# DigitalV0_1.net
KiCad netlist of a schematic drawn in Altium Designer
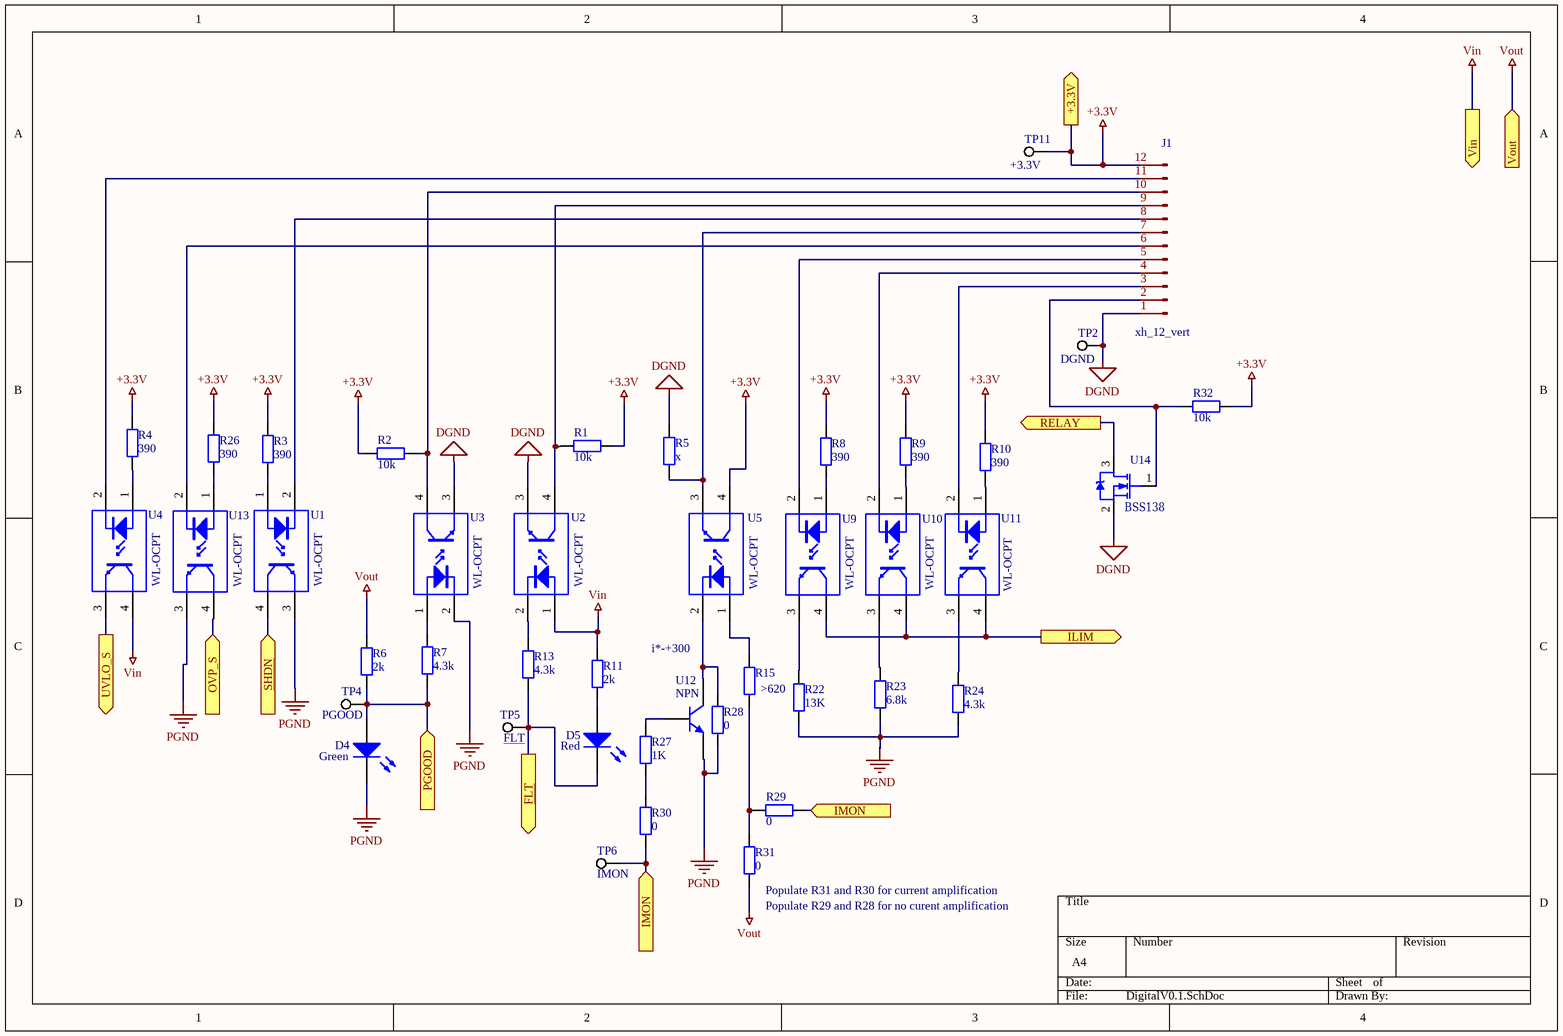
[diagram p0: DigitalV0.1.SchDoc]

(export (version "E")
  (design (tool "Eeschema 10.0.6"))
  (components
    (comp (ref "D4")
      (value "Green")
      (footprint "0805 LED")
      (libsource (lib "generic_components") (part "LED"))
    )
    (comp (ref "D5") (value "Red") (footprint "0805 LED") (libsource (lib "generic_components") (part "LED")))
    (comp (ref "J1")
      (value "xh_12_vert")
      (footprint "JST_XH_B12B-XH-A_1x12_P2.50mm_Vertical")
      (libsource (lib "JST") (part "xh_12_vert"))
    )
    (comp (ref "R1") (value "10k") (footprint "0805") (libsource (lib "") (part "res0805_2")))
    (comp (ref "R2") (value "10k") (footprint "0805") (libsource (lib "") (part "res0805_3")))
    (comp (ref "R3") (value "390") (footprint "0805") (libsource (lib "") (part "res0805_1")))
    (comp (ref "R4") (value "390") (footprint "0805") (libsource (lib "") (part "res0805_1")))
    (comp (ref "R5") (value "x") (footprint "0805") (libsource (lib "") (part "res0805_1")))
    (comp (ref "R6") (value "2k") (footprint "0805") (libsource (lib "") (part "res0805_1")))
    (comp (ref "R7") (value "4.3k") (footprint "0805") (libsource (lib "") (part "res0805_1")))
    (comp (ref "R8") (value "390") (footprint "0805") (libsource (lib "") (part "res0805_1")))
    (comp (ref "R9") (value "390") (footprint "0805") (libsource (lib "") (part "res0805_1")))
    (comp (ref "R10") (value "390") (footprint "0805") (libsource (lib "") (part "res0805_1")))
    (comp (ref "R11") (value "2k") (footprint "0805") (libsource (lib "") (part "res0805_1")))
    (comp (ref "R13") (value "4.3k") (footprint "0805") (libsource (lib "") (part "res0805_1")))
    (comp (ref "R15") (value ">620") (footprint "0805") (libsource (lib "") (part "res0805_1")))
    (comp (ref "R22") (value "13K") (footprint "0805") (libsource (lib "") (part "res0805_1")))
    (comp (ref "R23") (value "6.8k") (footprint "0805") (libsource (lib "") (part "res0805_1")))
    (comp (ref "R24") (value "4.3k") (footprint "0805") (libsource (lib "") (part "res0805_1")))
    (comp (ref "R26") (value "390") (footprint "0805") (libsource (lib "") (part "res0805_1")))
    (comp (ref "R27") (value "1K") (footprint "0805") (libsource (lib "generic_components") (part "res0805")))
    (comp (ref "R28") (value "0") (footprint "0805") (libsource (lib "generic_components") (part "res0805")))
    (comp (ref "R29") (value "0") (footprint "0805") (libsource (lib "") (part "res0805_2")))
    (comp (ref "R30") (value "0") (footprint "0805") (libsource (lib "generic_components") (part "res0805")))
    (comp (ref "R31") (value "0") (footprint "0805") (libsource (lib "generic_components") (part "res0805")))
    (comp (ref "R32") (value "10k") (footprint "0805") (libsource (lib "") (part "res0805_3")))
    (comp (ref "TP2")
      (value "DGND")
      (footprint "Test Loop 1.6mm")
      (libsource (lib "generic_components") (part "Test point"))
    )
    (comp (ref "TP4")
      (value "PGOOD")
      (footprint "Test Loop 1.6mm")
      (libsource (lib "generic_components") (part "Test point"))
    )
    (comp (ref "TP5")
      (value "FLT")
      (footprint "Test Loop 1.6mm")
      (libsource (lib "generic_components") (part "Test point"))
    )
    (comp (ref "TP6")
      (value "IMON")
      (footprint "Test Loop 1.6mm")
      (libsource (lib "generic_components") (part "Test point"))
    )
    (comp (ref "TP11")
      (value "+3.3V")
      (footprint "Test Loop 1.6mm")
      (libsource (lib "generic_components") (part "Test point"))
    )
    (comp (ref "U1")
      (value "WL-OCPT")
      (footprint "4-SOP_WE_opto-isolator")
      (libsource (lib "generic_components") (part "optoc WE"))
    )
    (comp (ref "U2")
      (value "WL-OCPT")
      (footprint "4-SOP_WE_opto-isolator")
      (libsource (lib "generic_components") (part "optoc WE"))
    )
    (comp (ref "U3")
      (value "WL-OCPT")
      (footprint "4-SOP_WE_opto-isolator")
      (libsource (lib "generic_components") (part "optoc WE"))
    )
    (comp (ref "U4")
      (value "WL-OCPT")
      (footprint "4-SOP_WE_opto-isolator")
      (libsource (lib "generic_components") (part "optoc WE"))
    )
    (comp (ref "U5")
      (value "WL-OCPT")
      (footprint "4-SOP_WE_opto-isolator")
      (libsource (lib "generic_components") (part "optoc WE"))
    )
    (comp (ref "U9")
      (value "WL-OCPT")
      (footprint "4-SOP_WE_opto-isolator")
      (libsource (lib "generic_components") (part "optoc WE"))
    )
    (comp (ref "U10")
      (value "WL-OCPT")
      (footprint "4-SOP_WE_opto-isolator")
      (libsource (lib "generic_components") (part "optoc WE"))
    )
    (comp (ref "U11")
      (value "WL-OCPT")
      (footprint "4-SOP_WE_opto-isolator")
      (libsource (lib "generic_components") (part "optoc WE"))
    )
    (comp (ref "U12")
      (value "NPN")
      (footprint "SOT23(TO-236AB)P095S230x290")
      (libsource (lib "generic_components") (part "NPN"))
    )
    (comp (ref "U13")
      (value "WL-OCPT")
      (footprint "4-SOP_WE_opto-isolator")
      (libsource (lib "generic_components") (part "optoc WE"))
    )
    (comp (ref "U14")
      (value "BSS138‎")
      (footprint "SOT-23-3")
      (libsource (lib "generic_components") (part "N-mosfet en"))
    )
  )
  (nets
    (net (code "1") (name "+3.3V") (class "Default")
      (node (ref "J1") (pin "12") (pinfunction "Pin_11_12") (pintype "passive"))
      (node (ref "R1") (pin "1") (pintype "passive"))
      (node (ref "R10") (pin "2") (pinfunction "2_2") (pintype "passive"))
      (node (ref "R2") (pin "1") (pintype "passive"))
      (node (ref "R26") (pin "2") (pinfunction "2_2") (pintype "passive"))
      (node (ref "R3") (pin "2") (pinfunction "2_2") (pintype "passive"))
      (node (ref "R32") (pin "2") (pinfunction "2_2") (pintype "passive"))
      (node (ref "R4") (pin "2") (pinfunction "2_2") (pintype "passive"))
      (node (ref "R8") (pin "2") (pinfunction "2_2") (pintype "passive"))
      (node (ref "R9") (pin "2") (pinfunction "2_2") (pintype "passive"))
      (node (ref "TP11") (pin "1") (pintype "passive"))
      (node (ref "U5") (pin "4") (pinfunction "C_4") (pintype "passive"))
    )
    (net (code "2") (name "/FLT") (class "Default")
      (node (ref "D5") (pin "2") (pinfunction "K_2") (pintype "passive"))
      (node (ref "R13") (pin "1") (pintype "passive"))
      (node (ref "TP5") (pin "1") (pintype "passive"))
    )
    (net (code "3") (name "/ILIM") (class "Default")
      (node (ref "U10") (pin "4") (pinfunction "C_4") (pintype "passive"))
      (node (ref "U11") (pin "4") (pinfunction "C_4") (pintype "passive"))
      (node (ref "U9") (pin "4") (pinfunction "C_4") (pintype "passive"))
    )
    (net (code "4") (name "/IMON") (class "Default")
      (node (ref "R29") (pin "1") (pintype "passive"))
      (node (ref "R30") (pin "2") (pinfunction "2_2") (pintype "passive"))
      (node (ref "TP6") (pin "1") (pintype "passive"))
    )
    (net (code "5") (name "/OVP_S") (class "Default")
      (node (ref "U13") (pin "4") (pinfunction "C_4") (pintype "passive"))
    )
    (net (code "6") (name "/PGOOD") (class "Default")
      (node (ref "D4") (pin "1") (pinfunction "A_1") (pintype "passive"))
      (node (ref "R6") (pin "1") (pintype "passive"))
      (node (ref "R7") (pin "1") (pintype "passive"))
      (node (ref "TP4") (pin "1") (pintype "passive"))
    )
    (net (code "7") (name "/RELAY") (class "Default")
      (node (ref "U14") (pin "3") (pinfunction "S_3") (pintype "passive"))
    )
    (net (code "8") (name "/SHDN") (class "Default")
      (node (ref "U1") (pin "4") (pinfunction "C_4") (pintype "passive"))
    )
    (net (code "9") (name "/UVLO_S") (class "Default")
      (node (ref "U4") (pin "3") (pinfunction "E_3") (pintype "passive"))
    )
    (net (code "10") (name "DGND") (class "Default")
      (node (ref "J1") (pin "1") (pinfunction "Pin_1_1") (pintype "passive"))
      (node (ref "R5") (pin "2") (pinfunction "2_2") (pintype "passive"))
      (node (ref "TP2") (pin "1") (pintype "passive"))
      (node (ref "U14") (pin "2") (pinfunction "D_2") (pintype "passive"))
      (node (ref "U2") (pin "3") (pinfunction "E_3") (pintype "passive"))
      (node (ref "U3") (pin "3") (pinfunction "E_3") (pintype "passive"))
    )
    (net (code "11") (name "Net-(D5-A)") (class "Default")
      (node (ref "D5") (pin "1") (pinfunction "A_1") (pintype "passive"))
      (node (ref "R11") (pin "1") (pintype "passive"))
    )
    (net (code "12") (name "Net-(J1-Pin_2)") (class "Default")
      (node (ref "J1") (pin "2") (pinfunction "Pin_2_2") (pintype "passive"))
      (node (ref "R32") (pin "1") (pintype "passive"))
      (node (ref "U14") (pin "1") (pinfunction "G_1") (pintype "passive"))
    )
    (net (code "13") (name "Net-(J1-Pin_3)") (class "Default")
      (node (ref "J1") (pin "3") (pinfunction "Pin_3_3") (pintype "passive"))
      (node (ref "U11") (pin "2") (pinfunction "C_2") (pintype "passive"))
    )
    (net (code "14") (name "Net-(J1-Pin_4)") (class "Default")
      (node (ref "J1") (pin "4") (pinfunction "Pin_4_4") (pintype "passive"))
      (node (ref "U10") (pin "2") (pinfunction "C_2") (pintype "passive"))
    )
    (net (code "15") (name "Net-(J1-Pin_5)") (class "Default")
      (node (ref "J1") (pin "5") (pinfunction "Pin_5_5") (pintype "passive"))
      (node (ref "U9") (pin "2") (pinfunction "C_2") (pintype "passive"))
    )
    (net (code "16") (name "Net-(J1-Pin_6)") (class "Default")
      (node (ref "J1") (pin "6") (pinfunction "Pin_6_6") (pintype "passive"))
      (node (ref "U13") (pin "2") (pinfunction "C_2") (pintype "passive"))
    )
    (net (code "17") (name "Net-(J1-Pin_7)") (class "Default")
      (node (ref "J1") (pin "7") (pinfunction "Pin_7_7") (pintype "passive"))
      (node (ref "R5") (pin "1") (pintype "passive"))
      (node (ref "U5") (pin "3") (pinfunction "E_3") (pintype "passive"))
    )
    (net (code "18") (name "Net-(J1-Pin_8)") (class "Default")
      (node (ref "J1") (pin "8") (pinfunction "Pin_8_8") (pintype "passive"))
      (node (ref "U1") (pin "2") (pinfunction "C_2") (pintype "passive"))
    )
    (net (code "19") (name "Net-(J1-Pin_9)") (class "Default")
      (node (ref "J1") (pin "9") (pinfunction "Pin_9_9") (pintype "passive"))
      (node (ref "R1") (pin "2") (pinfunction "2_2") (pintype "passive"))
      (node (ref "U2") (pin "4") (pinfunction "C_4") (pintype "passive"))
    )
    (net (code "20") (name "Net-(J1-Pin_10)") (class "Default")
      (node (ref "J1") (pin "10") (pinfunction "Pin_10_10") (pintype "passive"))
      (node (ref "R2") (pin "2") (pinfunction "2_2") (pintype "passive"))
      (node (ref "U3") (pin "4") (pinfunction "C_4") (pintype "passive"))
    )
    (net (code "21") (name "Net-(J1-Pin_11-Pad11)") (class "Default")
      (node (ref "J1") (pin "11") (pinfunction "Pin_11_11") (pintype "passive"))
      (node (ref "U4") (pin "2") (pinfunction "C_2") (pintype "passive"))
    )
    (net (code "22") (name "Net-(R13-Pad2)") (class "Default")
      (node (ref "R13") (pin "2") (pinfunction "2_2") (pintype "passive"))
      (node (ref "U2") (pin "2") (pinfunction "C_2") (pintype "passive"))
    )
    (net (code "23") (name "Net-(R15-Pad1)") (class "Default")
      (node (ref "R15") (pin "1") (pintype "passive"))
      (node (ref "R29") (pin "2") (pinfunction "2_2") (pintype "passive"))
      (node (ref "R31") (pin "1") (pintype "passive"))
    )
    (net (code "24") (name "Net-(R27-Pad2)") (class "Default")
      (node (ref "R27") (pin "2") (pinfunction "2_2") (pintype "passive"))
      (node (ref "R30") (pin "1") (pintype "passive"))
    )
    (net (code "25") (name "Net-(U1-A)") (class "Default")
      (node (ref "R3") (pin "1") (pintype "passive"))
      (node (ref "U1") (pin "1") (pinfunction "A_1") (pintype "passive"))
    )
    (net (code "26") (name "Net-(U3-A)") (class "Default")
      (node (ref "R7") (pin "2") (pinfunction "2_2") (pintype "passive"))
      (node (ref "U3") (pin "1") (pinfunction "A_1") (pintype "passive"))
    )
    (net (code "27") (name "Net-(U4-A)") (class "Default")
      (node (ref "R4") (pin "1") (pintype "passive"))
      (node (ref "U4") (pin "1") (pinfunction "A_1") (pintype "passive"))
    )
    (net (code "28") (name "Net-(U5-A)") (class "Default")
      (node (ref "R15") (pin "2") (pinfunction "2_2") (pintype "passive"))
      (node (ref "U5") (pin "1") (pinfunction "A_1") (pintype "passive"))
    )
    (net (code "29") (name "Net-(U9-A)") (class "Default")
      (node (ref "R8") (pin "1") (pintype "passive"))
      (node (ref "U9") (pin "1") (pinfunction "A_1") (pintype "passive"))
    )
    (net (code "30") (name "Net-(U9-E)") (class "Default")
      (node (ref "R22") (pin "2") (pinfunction "2_2") (pintype "passive"))
      (node (ref "U9") (pin "3") (pinfunction "E_3") (pintype "passive"))
    )
    (net (code "31") (name "Net-(U10-A)") (class "Default")
      (node (ref "R9") (pin "1") (pintype "passive"))
      (node (ref "U10") (pin "1") (pinfunction "A_1") (pintype "passive"))
    )
    (net (code "32") (name "Net-(U10-E)") (class "Default")
      (node (ref "R23") (pin "2") (pinfunction "2_2") (pintype "passive"))
      (node (ref "U10") (pin "3") (pinfunction "E_3") (pintype "passive"))
    )
    (net (code "33") (name "Net-(U11-A)") (class "Default")
      (node (ref "R10") (pin "1") (pintype "passive"))
      (node (ref "U11") (pin "1") (pinfunction "A_1") (pintype "passive"))
    )
    (net (code "34") (name "Net-(U11-E)") (class "Default")
      (node (ref "R24") (pin "2") (pinfunction "2_2") (pintype "passive"))
      (node (ref "U11") (pin "3") (pinfunction "E_3") (pintype "passive"))
    )
    (net (code "35") (name "Net-(U12-B)") (class "Default")
      (node (ref "R27") (pin "1") (pintype "passive"))
      (node (ref "U12") (pin "1") (pinfunction "B_1") (pintype "passive"))
    )
    (net (code "36") (name "Net-(U12-C)") (class "Default")
      (node (ref "R28") (pin "1") (pintype "passive"))
      (node (ref "U12") (pin "3") (pinfunction "C_3") (pintype "passive"))
      (node (ref "U5") (pin "2") (pinfunction "C_2") (pintype "passive"))
    )
    (net (code "37") (name "Net-(U13-A)") (class "Default")
      (node (ref "R26") (pin "1") (pintype "passive"))
      (node (ref "U13") (pin "1") (pinfunction "A_1") (pintype "passive"))
    )
    (net (code "38") (name "PGND") (class "Default")
      (node (ref "D4") (pin "2") (pinfunction "K_2") (pintype "passive"))
      (node (ref "R22") (pin "1") (pintype "passive"))
      (node (ref "R23") (pin "1") (pintype "passive"))
      (node (ref "R24") (pin "1") (pintype "passive"))
      (node (ref "R28") (pin "2") (pinfunction "2_2") (pintype "passive"))
      (node (ref "U1") (pin "3") (pinfunction "E_3") (pintype "passive"))
      (node (ref "U12") (pin "2") (pinfunction "E_2") (pintype "passive"))
      (node (ref "U13") (pin "3") (pinfunction "E_3") (pintype "passive"))
      (node (ref "U3") (pin "2") (pinfunction "C_2") (pintype "passive"))
    )
    (net (code "39") (name "Vin") (class "Default")
      (node (ref "R11") (pin "2") (pinfunction "2_2") (pintype "passive"))
      (node (ref "U2") (pin "1") (pinfunction "A_1") (pintype "passive"))
      (node (ref "U4") (pin "4") (pinfunction "C_4") (pintype "passive"))
    )
    (net (code "40") (name "Vout") (class "Default")
      (node (ref "R31") (pin "2") (pinfunction "2_2") (pintype "passive"))
      (node (ref "R6") (pin "2") (pinfunction "2_2") (pintype "passive"))
    )
  )
)
